# Ledrock.net
KiCad netlist of a schematic drawn in Altium Designer
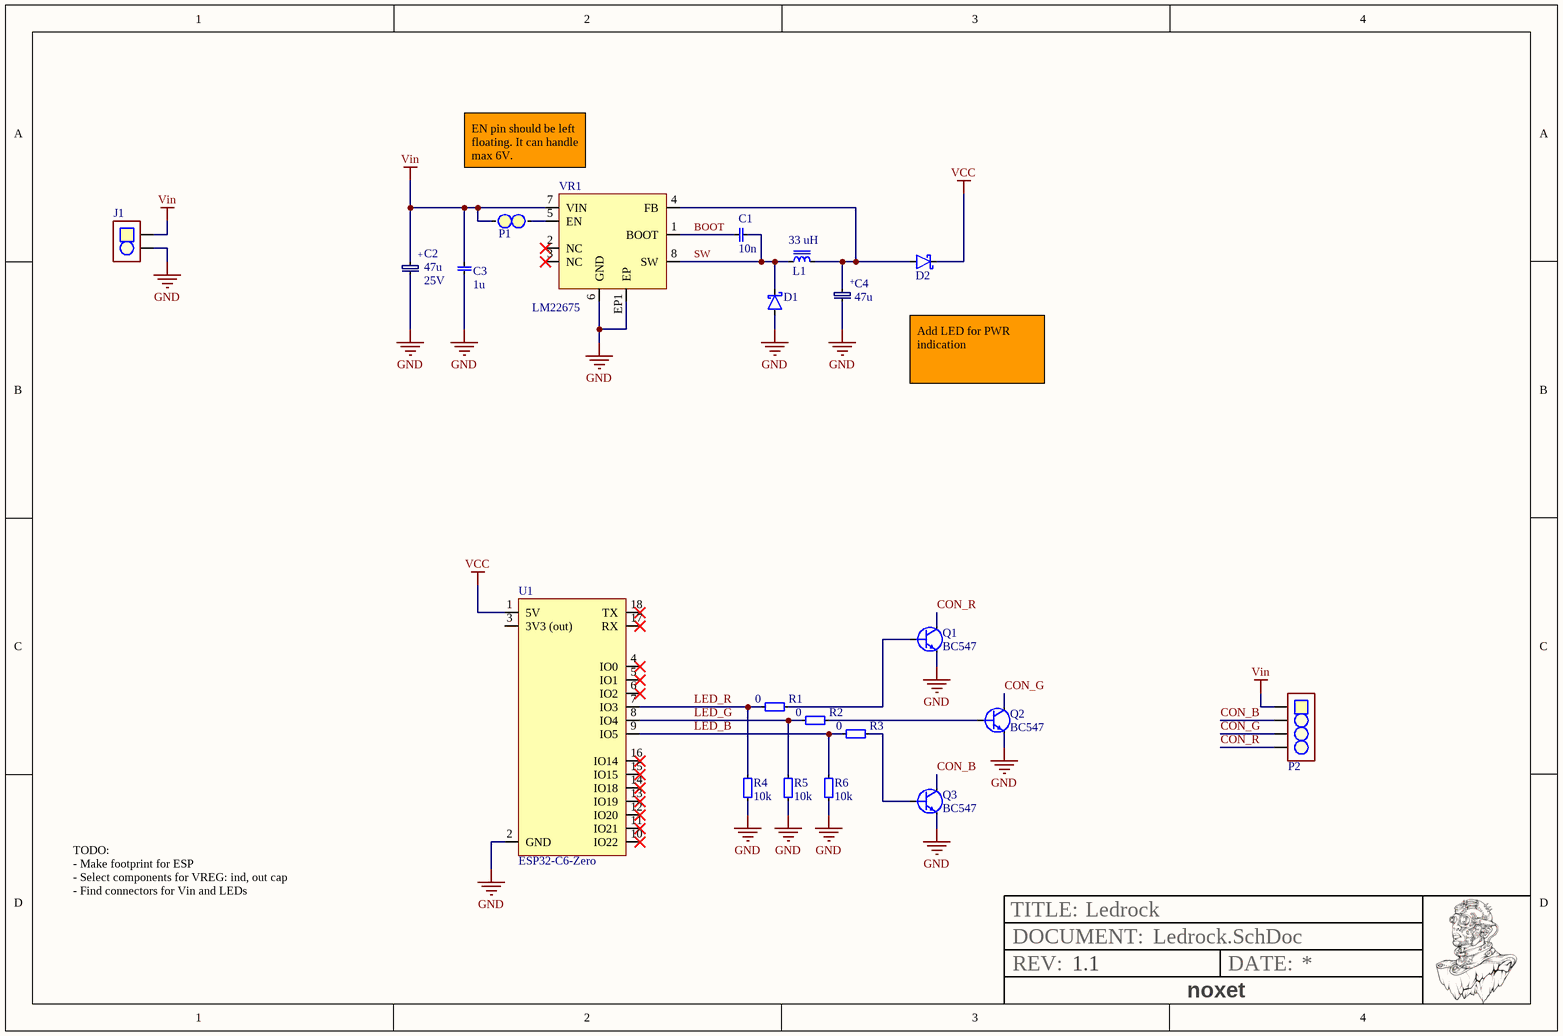
[diagram p0: Ledrock.SchDoc]

(export (version "E")
  (design (tool "Eeschema 10.0.6"))
  (components
    (comp (ref "C1")
      (value "10n")
      (footprint "0805, cap")
      (fields (field (name "Comment") "0805, capacitor"))
      (libsource (lib "Ledrock") (part "0805, capacitor"))
    )
    (comp (ref "C2")
      (value "25V")
      (footprint "Cap, SMD, Polar, 5.3x5.3mm")
      (description "Capacitor TH 2mm")
      (fields (field (name "ALTIUM_VALUE") "47u"))
      (libsource (lib "Ledrock") (part "Capacitor, TH 2mm"))
    )
    (comp (ref "C3")
      (value "1u")
      (footprint "0805, cap")
      (fields (field (name "Comment") "0805, capacitor"))
      (libsource (lib "Ledrock") (part "0805, capacitor"))
    )
    (comp (ref "C4")
      (value "47u")
      (footprint "Cap, SMD, Polar, 5.3x5.3mm")
      (description "Capacitor TH 2mm")
      (fields (field (name "Comment") "Capacitor, TH 2mm"))
      (libsource (lib "Ledrock") (part "Capacitor, TH 2mm"))
    )
    (comp (ref "D1")
      (value "MBRS2040LT3G")
      (footprint "CASE_403A")
      (description "Diode, Schottky Barrier, Vr 40V, If 2A, Pkg Smb, Vf 0.43V, Tj +125DEGC, Cs 70A, Ir 20MA")
      (libsource (lib "Ledrock") (part "MBRS2040LT3G"))
    )
    (comp (ref "D2")
      (value "B340A-E3/61T")
      (footprint "DO-214AC")
      (description "SchottkydiodE, 40 V, 3 A")
      (libsource (lib "jclib") (part "B340A-E3/61T"))
    )
    (comp (ref "J1")
      (value "OSTVN02A150")
      (footprint "2 Pole Block 2.54 mm TBC05")
      (fields (field (name "MANUFACTURER") "On Shore Technology"))
      (libsource (lib "Ledrock") (part "2 Pole Block Connector"))
    )
    (comp (ref "L1")
      (value "33 uH")
      (footprint "Inductor-SRN8040")
      (fields (field (name "MANUFACTURER PART NUMBER") "SRN8040-330M"))
      (libsource (lib "Ledrock") (part "Inductor"))
    )
    (comp (ref "P1")
      (value "1x2 Pin Heade Straight")
      (footprint "padtwo_L")
      (description "2.54 mm, TH")
      (libsource (lib "Ledrock") (part "1x2 Pin Heade Straight"))
    )
    (comp (ref "P2")
      (value "OSTVN04A150")
      (footprint "4 Pole Block 2.54mm TBC05")
      (description "1~24 Poles, Screwless, 45°, 3.50 Pitch, 24~20 (AWG), Terminal Block Connector")
      (fields (field (name "MANUFACTURER") "On Shore Technology"))
      (libsource (lib "Ledrock") (part "4 Pole Block Connector"))
    )
    (comp (ref "Q1")
      (value "BC547")
      (footprint "BC547_TO-92_BENT")
      (libsource (lib "Ledrock") (part "NPN CBE"))
    )
    (comp (ref "Q2")
      (value "BC547")
      (footprint "BC547_TO-92_BENT")
      (libsource (lib "Ledrock") (part "NPN CBE"))
    )
    (comp (ref "Q3")
      (value "BC547")
      (footprint "BC547_TO-92_BENT")
      (libsource (lib "Ledrock") (part "NPN CBE"))
    )
    (comp (ref "R1")
      (value "0")
      (footprint "0805")
      (fields (field (name "Comment") "General resistor"))
      (libsource (lib "Ledrock") (part "resistor"))
    )
    (comp (ref "R2")
      (value "0")
      (footprint "0805")
      (fields (field (name "Comment") "General resistor"))
      (libsource (lib "Ledrock") (part "resistor"))
    )
    (comp (ref "R3")
      (value "0")
      (footprint "0805")
      (fields (field (name "Comment") "General resistor"))
      (libsource (lib "Ledrock") (part "resistor"))
    )
    (comp (ref "R4")
      (value "10k")
      (footprint "0805")
      (fields (field (name "Comment") "General resistor"))
      (libsource (lib "Ledrock") (part "resistor"))
    )
    (comp (ref "R5")
      (value "10k")
      (footprint "0805")
      (fields (field (name "Comment") "General resistor"))
      (libsource (lib "Ledrock") (part "resistor"))
    )
    (comp (ref "R6")
      (value "10k")
      (footprint "0805")
      (fields (field (name "Comment") "General resistor"))
      (libsource (lib "Ledrock") (part "resistor"))
    )
    (comp (ref "U1")
      (value "ESP32-C6-Zero")
      (footprint "ESP32-C6-Zero")
      (description "Waveshare board with ESP32-C6FH4 MCU")
      (libsource (lib "Ledrock") (part "ESP32-C6-Zero"))
    )
    (comp (ref "VR1")
      (value "LM22675")
      (footprint "PowerPAD_Soic8")
      (description "4.5V to 42V, 1A SIMPLE SWITCHER® buck converter with precision enable 8-SO PowerPAD -40 to 125")
      (fields
        (field (name "MANUFACTURER") "Texas Instruments")
        (field (name "MANUFACTURER PART NUMBER") "LM22675MRX-5.0/NOPB")
      )
      (libsource (lib "jclib") (part "LM22675MRX-5.0/NOPB"))
    )
  )
  (nets
    (net (code "1") (name "/BOOT") (class "Default")
      (node (ref "C1") (pin "1") (pinfunction "1_1") (pintype "passive"))
      (node (ref "VR1") (pin "1") (pinfunction "BOOT_1") (pintype "passive"))
    )
    (net (code "2") (name "/CON_B") (class "Default")
      (node (ref "P2") (pin "2") (pinfunction "2_2") (pintype "passive"))
      (node (ref "Q3") (pin "1") (pinfunction "C_1") (pintype "passive"))
    )
    (net (code "3") (name "/CON_G") (class "Default")
      (node (ref "P2") (pin "3") (pinfunction "3_3") (pintype "passive"))
      (node (ref "Q2") (pin "1") (pinfunction "C_1") (pintype "passive"))
    )
    (net (code "4") (name "/CON_R") (class "Default")
      (node (ref "P2") (pin "4") (pinfunction "4_4") (pintype "passive"))
      (node (ref "Q1") (pin "1") (pinfunction "C_1") (pintype "passive"))
    )
    (net (code "5") (name "/LED_B") (class "Default")
      (node (ref "R3") (pin "1") (pinfunction "1_1") (pintype "passive"))
      (node (ref "R6") (pin "2") (pinfunction "2_2") (pintype "passive"))
      (node (ref "U1") (pin "9") (pinfunction "IO5_9") (pintype "passive"))
    )
    (net (code "6") (name "/LED_G") (class "Default")
      (node (ref "R2") (pin "1") (pinfunction "1_1") (pintype "passive"))
      (node (ref "R5") (pin "2") (pinfunction "2_2") (pintype "passive"))
      (node (ref "U1") (pin "8") (pinfunction "IO4_8") (pintype "passive"))
    )
    (net (code "7") (name "/LED_R") (class "Default")
      (node (ref "R1") (pin "1") (pinfunction "1_1") (pintype "passive"))
      (node (ref "R4") (pin "2") (pinfunction "2_2") (pintype "passive"))
      (node (ref "U1") (pin "7") (pinfunction "IO3_7") (pintype "passive"))
    )
    (net (code "8") (name "/SW") (class "Default")
      (node (ref "C1") (pin "2") (pinfunction "2_2") (pintype "passive"))
      (node (ref "D1") (pin "1") (pinfunction "K_1") (pintype "passive"))
      (node (ref "L1") (pin "2") (pinfunction "2_2") (pintype "passive"))
      (node (ref "VR1") (pin "8") (pinfunction "SW_8") (pintype "passive"))
    )
    (net (code "9") (name "GND") (class "Default")
      (node (ref "C2") (pin "1") (pinfunction "1_1") (pintype "passive"))
      (node (ref "C3") (pin "1") (pinfunction "1_1") (pintype "passive"))
      (node (ref "C4") (pin "1") (pinfunction "1_1") (pintype "passive"))
      (node (ref "D1") (pin "2") (pinfunction "A_2") (pintype "passive"))
      (node (ref "J1") (pin "2") (pinfunction "2_2") (pintype "passive"))
      (node (ref "Q1") (pin "3") (pinfunction "E_3") (pintype "passive"))
      (node (ref "Q2") (pin "3") (pinfunction "E_3") (pintype "passive"))
      (node (ref "Q3") (pin "3") (pinfunction "E_3") (pintype "passive"))
      (node (ref "R4") (pin "1") (pinfunction "1_1") (pintype "passive"))
      (node (ref "R5") (pin "1") (pinfunction "1_1") (pintype "passive"))
      (node (ref "R6") (pin "1") (pinfunction "1_1") (pintype "passive"))
      (node (ref "U1") (pin "2") (pinfunction "GND_2") (pintype "passive"))
      (node (ref "VR1") (pin "6") (pinfunction "GND_6") (pintype "passive"))
      (node (ref "VR1") (pin "EP1") (pinfunction "EP_EP1") (pintype "passive"))
    )
    (net (code "10") (name "Net-(D2-A)") (class "Default")
      (node (ref "C4") (pin "2") (pinfunction "2_2") (pintype "passive"))
      (node (ref "D2") (pin "2") (pinfunction "A_2") (pintype "passive"))
      (node (ref "L1") (pin "1") (pinfunction "1_1") (pintype "passive"))
      (node (ref "VR1") (pin "4") (pinfunction "FB_4") (pintype "passive"))
    )
    (net (code "11") (name "Net-(Q1-B)") (class "Default")
      (node (ref "Q1") (pin "2") (pinfunction "B_2") (pintype "passive"))
      (node (ref "R1") (pin "2") (pinfunction "2_2") (pintype "passive"))
    )
    (net (code "12") (name "Net-(Q2-B)") (class "Default")
      (node (ref "Q2") (pin "2") (pinfunction "B_2") (pintype "passive"))
      (node (ref "R2") (pin "2") (pinfunction "2_2") (pintype "passive"))
    )
    (net (code "13") (name "Net-(Q3-B)") (class "Default")
      (node (ref "Q3") (pin "2") (pinfunction "B_2") (pintype "passive"))
      (node (ref "R3") (pin "2") (pinfunction "2_2") (pintype "passive"))
    )
    (net (code "14") (name "Net-(VR1-EN)") (class "Default")
      (node (ref "P1") (pin "2") (pinfunction "2_2") (pintype "passive"))
      (node (ref "VR1") (pin "5") (pinfunction "EN_5") (pintype "passive"))
    )
    (net (code "15") (name "VCC") (class "Default")
      (node (ref "D2") (pin "1") (pinfunction "K_1") (pintype "passive"))
      (node (ref "U1") (pin "1") (pinfunction "5V_1") (pintype "passive"))
    )
    (net (code "16") (name "Vin") (class "Default")
      (node (ref "C2") (pin "2") (pinfunction "2_2") (pintype "passive"))
      (node (ref "C3") (pin "2") (pinfunction "2_2") (pintype "passive"))
      (node (ref "J1") (pin "1") (pinfunction "1_1") (pintype "passive"))
      (node (ref "P1") (pin "1") (pinfunction "1_1") (pintype "passive"))
      (node (ref "P2") (pin "1") (pinfunction "1_1") (pintype "passive"))
      (node (ref "VR1") (pin "7") (pinfunction "VIN_7") (pintype "passive"))
    )
    (net (code "17") (name "unconnected-(U1-3V3_(out)-Pad3)") (class "Default")
      (node (ref "U1") (pin "3") (pinfunction "3V3_(out)_3") (pintype "passive"))
    )
    (net (code "18") (name "unconnected-(U1-IO0-Pad4)") (class "Default")
      (node (ref "U1") (pin "4") (pinfunction "IO0_4") (pintype "passive+no_connect"))
    )
    (net (code "19") (name "unconnected-(U1-IO1-Pad5)") (class "Default")
      (node (ref "U1") (pin "5") (pinfunction "IO1_5") (pintype "passive+no_connect"))
    )
    (net (code "20") (name "unconnected-(U1-IO2-Pad6)") (class "Default")
      (node (ref "U1") (pin "6") (pinfunction "IO2_6") (pintype "passive+no_connect"))
    )
    (net (code "21") (name "unconnected-(U1-IO14-Pad16)") (class "Default")
      (node (ref "U1") (pin "16") (pinfunction "IO14_16") (pintype "passive+no_connect"))
    )
    (net (code "22") (name "unconnected-(U1-IO15-Pad15)") (class "Default")
      (node (ref "U1") (pin "15") (pinfunction "IO15_15") (pintype "passive+no_connect"))
    )
    (net (code "23") (name "unconnected-(U1-IO18-Pad14)") (class "Default")
      (node (ref "U1") (pin "14") (pinfunction "IO18_14") (pintype "passive+no_connect"))
    )
    (net (code "24") (name "unconnected-(U1-IO19-Pad13)") (class "Default")
      (node (ref "U1") (pin "13") (pinfunction "IO19_13") (pintype "passive+no_connect"))
    )
    (net (code "25") (name "unconnected-(U1-IO20-Pad12)") (class "Default")
      (node (ref "U1") (pin "12") (pinfunction "IO20_12") (pintype "passive+no_connect"))
    )
    (net (code "26") (name "unconnected-(U1-IO21-Pad11)") (class "Default")
      (node (ref "U1") (pin "11") (pinfunction "IO21_11") (pintype "passive+no_connect"))
    )
    (net (code "27") (name "unconnected-(U1-IO22-Pad10)") (class "Default")
      (node (ref "U1") (pin "10") (pinfunction "IO22_10") (pintype "passive+no_connect"))
    )
    (net (code "28") (name "unconnected-(U1-RX-Pad17)") (class "Default")
      (node (ref "U1") (pin "17") (pinfunction "RX_17") (pintype "passive+no_connect"))
    )
    (net (code "29") (name "unconnected-(U1-TX-Pad18)") (class "Default")
      (node (ref "U1") (pin "18") (pinfunction "TX_18") (pintype "passive+no_connect"))
    )
    (net (code "30") (name "unconnected-(VR1-NC-Pad2)") (class "Default")
      (node (ref "VR1") (pin "2") (pinfunction "NC_2") (pintype "passive+no_connect"))
    )
    (net (code "31") (name "unconnected-(VR1-NC-Pad3)") (class "Default")
      (node (ref "VR1") (pin "3") (pinfunction "NC_3") (pintype "passive+no_connect"))
    )
  )
)
